# HydrophoneGroup2FilterAndAmpCircuit.net
KiCad netlist of a schematic drawn in Altium Designer
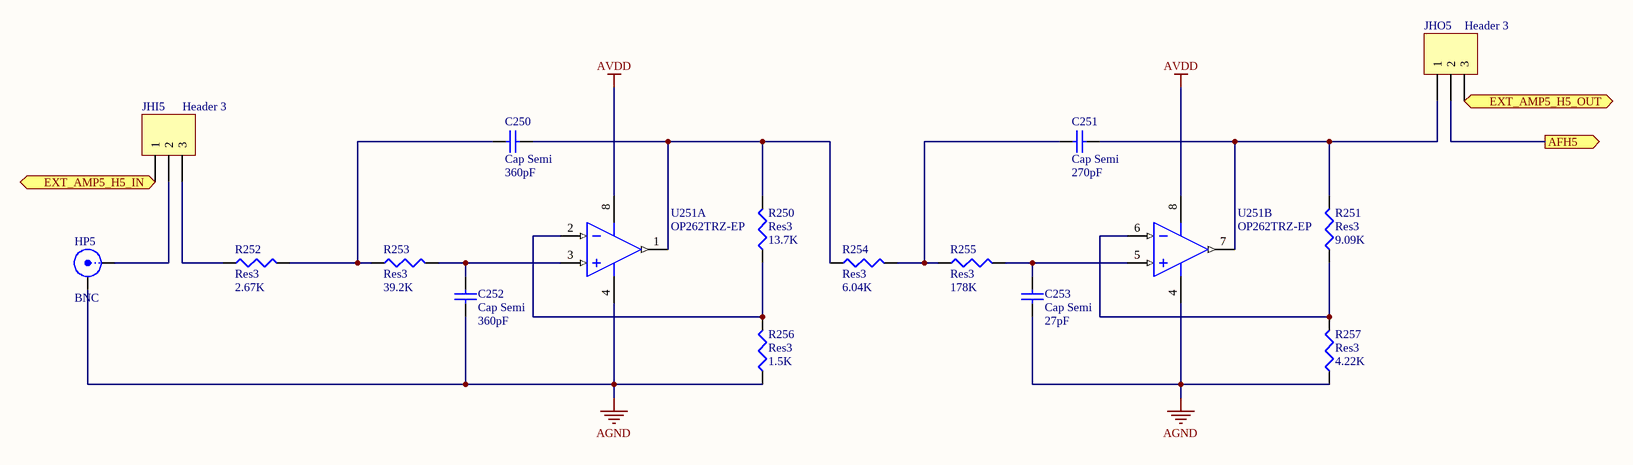
[diagram p0: HydrophoneGroup2FilterAndAmpCircuit.SchDoc]

(export (version "E")
  (design (tool "Eeschema 10.0.6"))
  (components
    (comp (ref "C250")
      (value "Cap Semi")
      (footprint "1608[0603]")
      (description "Capacitor (Semiconductor SIM Model)")
      (fields (field (name "ALTIUM_VALUE") "360pF") (field (name "PUBLISHER") "Altium Limited"))
      (libsource (lib "Miscellaneous Devices") (part "Cap Semi"))
    )
    (comp (ref "C251")
      (value "Cap Semi")
      (footprint "1608[0603]")
      (description "Capacitor (Semiconductor SIM Model)")
      (fields (field (name "ALTIUM_VALUE") "270pF") (field (name "PUBLISHER") "Altium Limited"))
      (libsource (lib "Miscellaneous Devices") (part "Cap Semi"))
    )
    (comp (ref "C252")
      (value "Cap Semi")
      (footprint "1608[0603]")
      (description "Capacitor (Semiconductor SIM Model)")
      (fields (field (name "ALTIUM_VALUE") "360pF") (field (name "PUBLISHER") "Altium Limited"))
      (libsource (lib "Miscellaneous Devices") (part "Cap Semi"))
    )
    (comp (ref "C253")
      (value "Cap Semi")
      (footprint "1608[0603]")
      (description "Capacitor (Semiconductor SIM Model)")
      (fields (field (name "ALTIUM_VALUE") "27pF") (field (name "PUBLISHER") "Altium Limited"))
      (libsource (lib "Miscellaneous Devices") (part "Cap Semi"))
    )
    (comp (ref "HP5")
      (value "BNC")
      (footprint "BNC_RA CON")
      (description "BNC Elbow Connector")
      (fields (field (name "PUBLISHER") "Altium Limited"))
      (libsource (lib "Miscellaneous Connectors") (part "BNC"))
    )
    (comp (ref "JHI5")
      (value "Header 3")
      (footprint "HDR1X3")
      (description "Header, 3-Pin")
      (fields (field (name "PUBLISHER") "Altium Limited"))
      (libsource (lib "Miscellaneous Connectors") (part "Header 3"))
    )
    (comp (ref "JHO5")
      (value "Header 3")
      (footprint "HDR1X3")
      (description "Header, 3-Pin")
      (fields (field (name "PUBLISHER") "Altium Limited"))
      (libsource (lib "Miscellaneous Connectors") (part "Header 3"))
    )
    (comp (ref "R250")
      (value "Res3")
      (footprint "J1-0603")
      (description "Resistor")
      (fields (field (name "ALTIUM_VALUE") "13.7K") (field (name "PUBLISHER") "Altium Limited"))
      (libsource (lib "Miscellaneous Devices") (part "Res3"))
    )
    (comp (ref "R251")
      (value "Res3")
      (footprint "J1-0603")
      (description "Resistor")
      (fields (field (name "ALTIUM_VALUE") "9.09K") (field (name "PUBLISHER") "Altium Limited"))
      (libsource (lib "Miscellaneous Devices") (part "Res3"))
    )
    (comp (ref "R252")
      (value "Res3")
      (footprint "J1-0603")
      (description "Resistor")
      (fields (field (name "ALTIUM_VALUE") "2.67K") (field (name "PUBLISHER") "Altium Limited"))
      (libsource (lib "Miscellaneous Devices") (part "Res3"))
    )
    (comp (ref "R253")
      (value "Res3")
      (footprint "J1-0603")
      (description "Resistor")
      (fields (field (name "ALTIUM_VALUE") "39.2K") (field (name "PUBLISHER") "Altium Limited"))
      (libsource (lib "Miscellaneous Devices") (part "Res3"))
    )
    (comp (ref "R254")
      (value "Res3")
      (footprint "J1-0603")
      (description "Resistor")
      (fields (field (name "ALTIUM_VALUE") "6.04K") (field (name "PUBLISHER") "Altium Limited"))
      (libsource (lib "Miscellaneous Devices") (part "Res3"))
    )
    (comp (ref "R255")
      (value "Res3")
      (footprint "J1-0603")
      (description "Resistor")
      (fields (field (name "ALTIUM_VALUE") "178K") (field (name "PUBLISHER") "Altium Limited"))
      (libsource (lib "Miscellaneous Devices") (part "Res3"))
    )
    (comp (ref "R256")
      (value "Res3")
      (footprint "J1-0603")
      (description "Resistor")
      (fields (field (name "ALTIUM_VALUE") "1.5K") (field (name "PUBLISHER") "Altium Limited"))
      (libsource (lib "Miscellaneous Devices") (part "Res3"))
    )
    (comp (ref "R257")
      (value "Res3")
      (footprint "J1-0603")
      (description "Resistor")
      (fields (field (name "ALTIUM_VALUE") "4.22K") (field (name "PUBLISHER") "Altium Limited"))
      (libsource (lib "Miscellaneous Devices") (part "Res3"))
    )
    (comp (ref "U251")
      (value "OP262TRZ-EP")
      (footprint "ADI-R-8_N")
      (fields (field (name "GENERIC PART NUMBER") "OP262") (field (name "MANUFACTURER") "Analog Devices"))
      (libsource (lib "Analog Devices Operational Amplifiers") (part "OP262TRZ-EP"))
    )
  )
  (nets
    (net (code "1") (name "/AFH5") (class "Default")
      (node (ref "JHO5") (pin "2") (pinfunction "2_2") (pintype "passive"))
    )
    (net (code "2") (name "/EXT_AMP5_H5_IN") (class "Default")
      (node (ref "JHI5") (pin "1") (pinfunction "1_1") (pintype "passive"))
    )
    (net (code "3") (name "/EXT_AMP5_H5_OUT") (class "Default")
      (node (ref "JHO5") (pin "3") (pinfunction "3_3") (pintype "passive"))
    )
    (net (code "4") (name "AGND") (class "Default")
      (node (ref "C252") (pin "1") (pinfunction "1_1") (pintype "passive"))
      (node (ref "C253") (pin "1") (pinfunction "1_1") (pintype "passive"))
      (node (ref "HP5") (pin "2") (pinfunction "Y_2") (pintype "passive"))
      (node (ref "R256") (pin "1") (pinfunction "1_1") (pintype "passive"))
      (node (ref "R257") (pin "1") (pinfunction "1_1") (pintype "passive"))
      (node (ref "U251") (pin "4") (pinfunction "-V_4") (pintype "power_in"))
    )
    (net (code "5") (name "AVDD") (class "Default")
      (node (ref "U251") (pin "8") (pinfunction "+V_8") (pintype "power_in"))
    )
    (net (code "6") (name "Net-(C250-Pad1)") (class "Default")
      (node (ref "C250") (pin "1") (pinfunction "1_1") (pintype "passive"))
      (node (ref "R252") (pin "2") (pinfunction "2_2") (pintype "passive"))
      (node (ref "R253") (pin "1") (pinfunction "1_1") (pintype "passive"))
    )
    (net (code "7") (name "Net-(C251-Pad1)") (class "Default")
      (node (ref "C251") (pin "1") (pinfunction "1_1") (pintype "passive"))
      (node (ref "R254") (pin "2") (pinfunction "2_2") (pintype "passive"))
      (node (ref "R255") (pin "1") (pinfunction "1_1") (pintype "passive"))
    )
    (net (code "8") (name "Net-(HP5-X)") (class "Default")
      (node (ref "HP5") (pin "1") (pinfunction "X_1") (pintype "passive"))
      (node (ref "JHI5") (pin "2") (pinfunction "2_2") (pintype "passive"))
    )
    (net (code "9") (name "Net-(JHI5-Pad3)") (class "Default")
      (node (ref "JHI5") (pin "3") (pinfunction "3_3") (pintype "passive"))
      (node (ref "R252") (pin "1") (pinfunction "1_1") (pintype "passive"))
    )
    (net (code "10") (name "Net-(U251A-+IN_A)") (class "Default")
      (node (ref "C252") (pin "2") (pinfunction "2_2") (pintype "passive"))
      (node (ref "R253") (pin "2") (pinfunction "2_2") (pintype "passive"))
      (node (ref "U251") (pin "3") (pinfunction "+IN_A_3") (pintype "input"))
    )
    (net (code "11") (name "Net-(U251A--IN_A)") (class "Default")
      (node (ref "R250") (pin "1") (pinfunction "1_1") (pintype "passive"))
      (node (ref "R256") (pin "2") (pinfunction "2_2") (pintype "passive"))
      (node (ref "U251") (pin "2") (pinfunction "-IN_A_2") (pintype "input"))
    )
    (net (code "12") (name "Net-(U251A-OUT_A)") (class "Default")
      (node (ref "C250") (pin "2") (pinfunction "2_2") (pintype "passive"))
      (node (ref "R250") (pin "2") (pinfunction "2_2") (pintype "passive"))
      (node (ref "R254") (pin "1") (pinfunction "1_1") (pintype "passive"))
      (node (ref "U251") (pin "1") (pinfunction "OUT_A_1") (pintype "output"))
    )
    (net (code "13") (name "Net-(U251B-+IN_B)") (class "Default")
      (node (ref "C253") (pin "2") (pinfunction "2_2") (pintype "passive"))
      (node (ref "R255") (pin "2") (pinfunction "2_2") (pintype "passive"))
      (node (ref "U251") (pin "5") (pinfunction "+IN_B_5") (pintype "input"))
    )
    (net (code "14") (name "Net-(U251B--IN_B)") (class "Default")
      (node (ref "R251") (pin "1") (pinfunction "1_1") (pintype "passive"))
      (node (ref "R257") (pin "2") (pinfunction "2_2") (pintype "passive"))
      (node (ref "U251") (pin "6") (pinfunction "-IN_B_6") (pintype "input"))
    )
    (net (code "15") (name "Net-(U251B-OUT_B)") (class "Default")
      (node (ref "C251") (pin "2") (pinfunction "2_2") (pintype "passive"))
      (node (ref "JHO5") (pin "1") (pinfunction "1_1") (pintype "passive"))
      (node (ref "R251") (pin "2") (pinfunction "2_2") (pintype "passive"))
      (node (ref "U251") (pin "7") (pinfunction "OUT_B_7") (pintype "output"))
    )
  )
)
